# WS2812B.net
KiCad netlist of a schematic drawn in Altium Designer
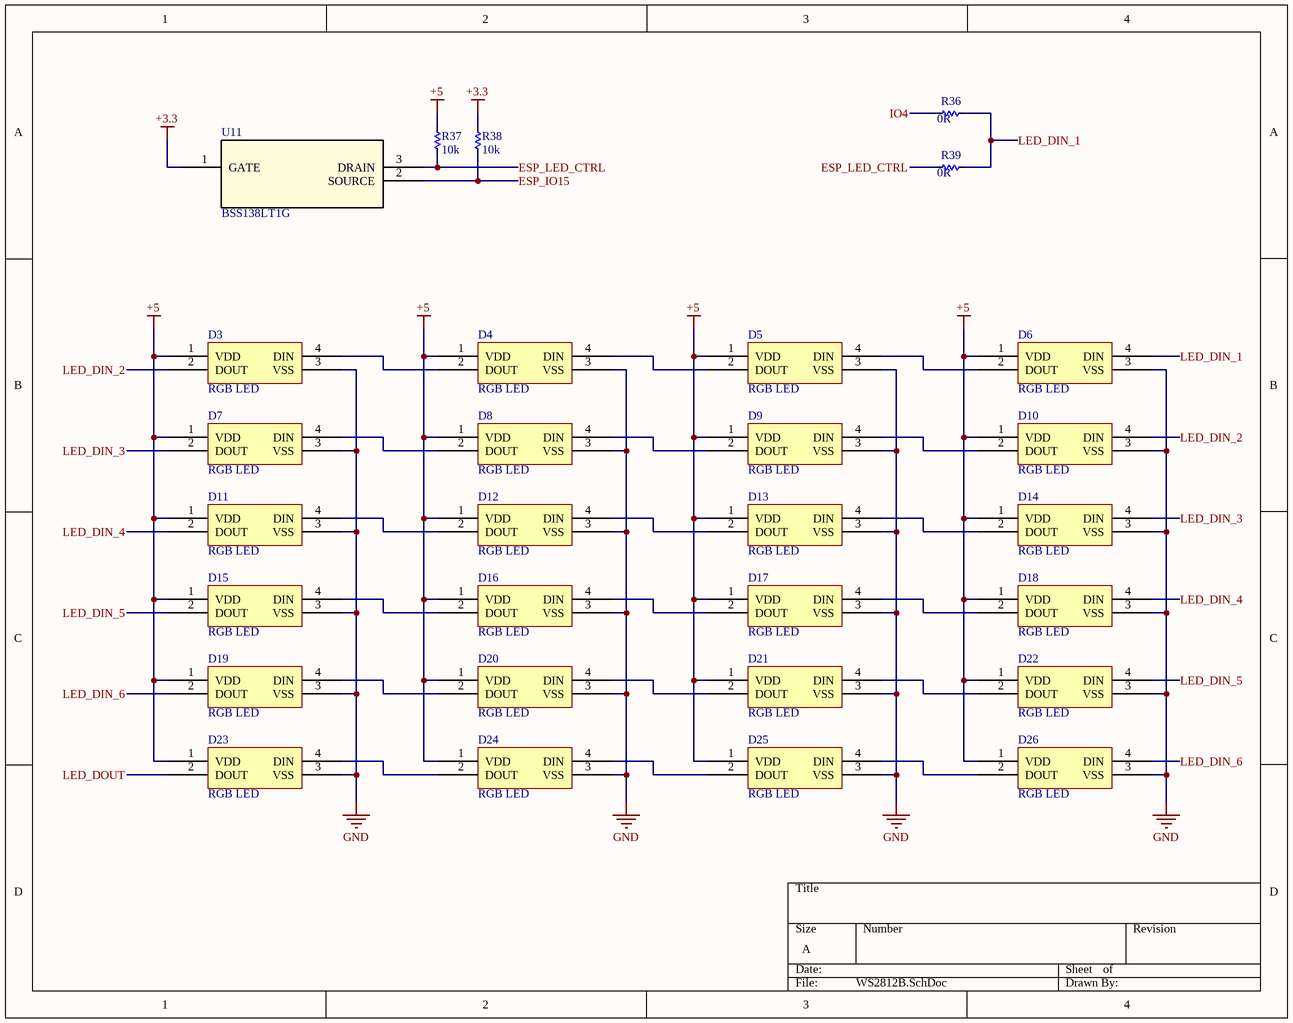
[diagram p0: WS2812B.SchDoc]

(export (version "E")
  (design (tool "Eeschema 10.0.6"))
  (components
    (comp (ref "D3")
      (value "RGB LED")
      (footprint "WS2812B")
      (description "RGB 620~630nm Red, 515~530nm Green, 465~475nm Blue SMD,5x5mm Light Emitting Diodes (LED) ROHS")
      (fields (field (name "MANUFACTURER") "Worldsemi"))
      (libsource (lib "WS2812B") (part "WS2812B"))
    )
    (comp (ref "D4")
      (value "RGB LED")
      (footprint "WS2812B")
      (description "RGB 620~630nm Red, 515~530nm Green, 465~475nm Blue SMD,5x5mm Light Emitting Diodes (LED) ROHS")
      (fields (field (name "MANUFACTURER") "Worldsemi"))
      (libsource (lib "WS2812B") (part "WS2812B"))
    )
    (comp (ref "D5")
      (value "RGB LED")
      (footprint "WS2812B")
      (description "RGB 620~630nm Red, 515~530nm Green, 465~475nm Blue SMD,5x5mm Light Emitting Diodes (LED) ROHS")
      (fields (field (name "MANUFACTURER") "Worldsemi"))
      (libsource (lib "WS2812B") (part "WS2812B"))
    )
    (comp (ref "D6")
      (value "RGB LED")
      (footprint "WS2812B")
      (description "RGB 620~630nm Red, 515~530nm Green, 465~475nm Blue SMD,5x5mm Light Emitting Diodes (LED) ROHS")
      (fields (field (name "MANUFACTURER") "Worldsemi"))
      (libsource (lib "WS2812B") (part "WS2812B"))
    )
    (comp (ref "D7")
      (value "RGB LED")
      (footprint "WS2812B")
      (description "RGB 620~630nm Red, 515~530nm Green, 465~475nm Blue SMD,5x5mm Light Emitting Diodes (LED) ROHS")
      (fields (field (name "MANUFACTURER") "Worldsemi"))
      (libsource (lib "WS2812B") (part "WS2812B"))
    )
    (comp (ref "D8")
      (value "RGB LED")
      (footprint "WS2812B")
      (description "RGB 620~630nm Red, 515~530nm Green, 465~475nm Blue SMD,5x5mm Light Emitting Diodes (LED) ROHS")
      (fields (field (name "MANUFACTURER") "Worldsemi"))
      (libsource (lib "WS2812B") (part "WS2812B"))
    )
    (comp (ref "D9")
      (value "RGB LED")
      (footprint "WS2812B")
      (description "RGB 620~630nm Red, 515~530nm Green, 465~475nm Blue SMD,5x5mm Light Emitting Diodes (LED) ROHS")
      (fields (field (name "MANUFACTURER") "Worldsemi"))
      (libsource (lib "WS2812B") (part "WS2812B"))
    )
    (comp (ref "D10")
      (value "RGB LED")
      (footprint "WS2812B")
      (description "RGB 620~630nm Red, 515~530nm Green, 465~475nm Blue SMD,5x5mm Light Emitting Diodes (LED) ROHS")
      (fields (field (name "MANUFACTURER") "Worldsemi"))
      (libsource (lib "WS2812B") (part "WS2812B"))
    )
    (comp (ref "D11")
      (value "RGB LED")
      (footprint "WS2812B")
      (description "RGB 620~630nm Red, 515~530nm Green, 465~475nm Blue SMD,5x5mm Light Emitting Diodes (LED) ROHS")
      (fields (field (name "MANUFACTURER") "Worldsemi"))
      (libsource (lib "WS2812B") (part "WS2812B"))
    )
    (comp (ref "D12")
      (value "RGB LED")
      (footprint "WS2812B")
      (description "RGB 620~630nm Red, 515~530nm Green, 465~475nm Blue SMD,5x5mm Light Emitting Diodes (LED) ROHS")
      (fields (field (name "MANUFACTURER") "Worldsemi"))
      (libsource (lib "WS2812B") (part "WS2812B"))
    )
    (comp (ref "D13")
      (value "RGB LED")
      (footprint "WS2812B")
      (description "RGB 620~630nm Red, 515~530nm Green, 465~475nm Blue SMD,5x5mm Light Emitting Diodes (LED) ROHS")
      (fields (field (name "MANUFACTURER") "Worldsemi"))
      (libsource (lib "WS2812B") (part "WS2812B"))
    )
    (comp (ref "D14")
      (value "RGB LED")
      (footprint "WS2812B")
      (description "RGB 620~630nm Red, 515~530nm Green, 465~475nm Blue SMD,5x5mm Light Emitting Diodes (LED) ROHS")
      (fields (field (name "MANUFACTURER") "Worldsemi"))
      (libsource (lib "WS2812B") (part "WS2812B"))
    )
    (comp (ref "D15")
      (value "RGB LED")
      (footprint "WS2812B")
      (description "RGB 620~630nm Red, 515~530nm Green, 465~475nm Blue SMD,5x5mm Light Emitting Diodes (LED) ROHS")
      (fields (field (name "MANUFACTURER") "Worldsemi"))
      (libsource (lib "WS2812B") (part "WS2812B"))
    )
    (comp (ref "D16")
      (value "RGB LED")
      (footprint "WS2812B")
      (description "RGB 620~630nm Red, 515~530nm Green, 465~475nm Blue SMD,5x5mm Light Emitting Diodes (LED) ROHS")
      (fields (field (name "MANUFACTURER") "Worldsemi"))
      (libsource (lib "WS2812B") (part "WS2812B"))
    )
    (comp (ref "D17")
      (value "RGB LED")
      (footprint "WS2812B")
      (description "RGB 620~630nm Red, 515~530nm Green, 465~475nm Blue SMD,5x5mm Light Emitting Diodes (LED) ROHS")
      (fields (field (name "MANUFACTURER") "Worldsemi"))
      (libsource (lib "WS2812B") (part "WS2812B"))
    )
    (comp (ref "D18")
      (value "RGB LED")
      (footprint "WS2812B")
      (description "RGB 620~630nm Red, 515~530nm Green, 465~475nm Blue SMD,5x5mm Light Emitting Diodes (LED) ROHS")
      (fields (field (name "MANUFACTURER") "Worldsemi"))
      (libsource (lib "WS2812B") (part "WS2812B"))
    )
    (comp (ref "D19")
      (value "RGB LED")
      (footprint "WS2812B")
      (description "RGB 620~630nm Red, 515~530nm Green, 465~475nm Blue SMD,5x5mm Light Emitting Diodes (LED) ROHS")
      (fields (field (name "MANUFACTURER") "Worldsemi"))
      (libsource (lib "WS2812B") (part "WS2812B"))
    )
    (comp (ref "D20")
      (value "RGB LED")
      (footprint "WS2812B")
      (description "RGB 620~630nm Red, 515~530nm Green, 465~475nm Blue SMD,5x5mm Light Emitting Diodes (LED) ROHS")
      (fields (field (name "MANUFACTURER") "Worldsemi"))
      (libsource (lib "WS2812B") (part "WS2812B"))
    )
    (comp (ref "D21")
      (value "RGB LED")
      (footprint "WS2812B")
      (description "RGB 620~630nm Red, 515~530nm Green, 465~475nm Blue SMD,5x5mm Light Emitting Diodes (LED) ROHS")
      (fields (field (name "MANUFACTURER") "Worldsemi"))
      (libsource (lib "WS2812B") (part "WS2812B"))
    )
    (comp (ref "D22")
      (value "RGB LED")
      (footprint "WS2812B")
      (description "RGB 620~630nm Red, 515~530nm Green, 465~475nm Blue SMD,5x5mm Light Emitting Diodes (LED) ROHS")
      (fields (field (name "MANUFACTURER") "Worldsemi"))
      (libsource (lib "WS2812B") (part "WS2812B"))
    )
    (comp (ref "D23")
      (value "RGB LED")
      (footprint "WS2812B")
      (description "RGB 620~630nm Red, 515~530nm Green, 465~475nm Blue SMD,5x5mm Light Emitting Diodes (LED) ROHS")
      (fields (field (name "MANUFACTURER") "Worldsemi"))
      (libsource (lib "WS2812B") (part "WS2812B"))
    )
    (comp (ref "D24")
      (value "RGB LED")
      (footprint "WS2812B")
      (description "RGB 620~630nm Red, 515~530nm Green, 465~475nm Blue SMD,5x5mm Light Emitting Diodes (LED) ROHS")
      (fields (field (name "MANUFACTURER") "Worldsemi"))
      (libsource (lib "WS2812B") (part "WS2812B"))
    )
    (comp (ref "D25")
      (value "RGB LED")
      (footprint "WS2812B")
      (description "RGB 620~630nm Red, 515~530nm Green, 465~475nm Blue SMD,5x5mm Light Emitting Diodes (LED) ROHS")
      (fields (field (name "MANUFACTURER") "Worldsemi"))
      (libsource (lib "WS2812B") (part "WS2812B"))
    )
    (comp (ref "D26")
      (value "RGB LED")
      (footprint "WS2812B")
      (description "RGB 620~630nm Red, 515~530nm Green, 465~475nm Blue SMD,5x5mm Light Emitting Diodes (LED) ROHS")
      (fields (field (name "MANUFACTURER") "Worldsemi"))
      (libsource (lib "WS2812B") (part "WS2812B"))
    )
    (comp (ref "R36")
      (value "0R")
      (footprint "RES-SMD-0603")
      (description "Resistor")
      (fields
        (field (name "MANUFACTURER") "Generic Components")
        (field (name "Comment") "Res")
        (field (name "PUBLISHER") "Altium Hobart Technology Centre")
      )
      (libsource (lib "LIBRARY") (part "Res-SMD"))
    )
    (comp (ref "R37")
      (value "10k")
      (footprint "RES-SMD-0603")
      (description "Resistor")
      (fields
        (field (name "MANUFACTURER") "Generic Components")
        (field (name "Comment") "Res")
        (field (name "PUBLISHER") "Altium Hobart Technology Centre")
      )
      (libsource (lib "LIBRARY") (part "Res-SMD"))
    )
    (comp (ref "R38")
      (value "10k")
      (footprint "RES-SMD-0603")
      (description "Resistor")
      (fields
        (field (name "MANUFACTURER") "Generic Components")
        (field (name "Comment") "Res")
        (field (name "PUBLISHER") "Altium Hobart Technology Centre")
      )
      (libsource (lib "LIBRARY") (part "Res-SMD"))
    )
    (comp (ref "R39")
      (value "0R")
      (footprint "RES-SMD-0603")
      (description "Resistor")
      (fields
        (field (name "MANUFACTURER") "Generic Components")
        (field (name "Comment") "Res")
        (field (name "PUBLISHER") "Altium Hobart Technology Centre")
      )
      (libsource (lib "LIBRARY") (part "Res-SMD"))
    )
    (comp (ref "U11")
      (value "BSS138LT1G")
      (footprint "SOT23-3_ONS")
      (description "No Description Available")
      (fields (field (name "COPYRIGHT") "Copyright (C) 2018 Accelerated Designs. All rights reserved"))
      (libsource (lib "BSS138LT1G") (part "BSS138LT1G"))
    )
  )
  (nets
    (net (code "1") (name "+3.3") (class "Default")
      (node (ref "R38") (pin "1") (pinfunction "1_1") (pintype "passive"))
      (node (ref "U11") (pin "1") (pinfunction "GATE_1") (pintype "passive"))
    )
    (net (code "2") (name "+5") (class "Default")
      (node (ref "D10") (pin "1") (pinfunction "VDD_1") (pintype "passive"))
      (node (ref "D11") (pin "1") (pinfunction "VDD_1") (pintype "passive"))
      (node (ref "D12") (pin "1") (pinfunction "VDD_1") (pintype "passive"))
      (node (ref "D13") (pin "1") (pinfunction "VDD_1") (pintype "passive"))
      (node (ref "D14") (pin "1") (pinfunction "VDD_1") (pintype "passive"))
      (node (ref "D15") (pin "1") (pinfunction "VDD_1") (pintype "passive"))
      (node (ref "D16") (pin "1") (pinfunction "VDD_1") (pintype "passive"))
      (node (ref "D17") (pin "1") (pinfunction "VDD_1") (pintype "passive"))
      (node (ref "D18") (pin "1") (pinfunction "VDD_1") (pintype "passive"))
      (node (ref "D19") (pin "1") (pinfunction "VDD_1") (pintype "passive"))
      (node (ref "D20") (pin "1") (pinfunction "VDD_1") (pintype "passive"))
      (node (ref "D21") (pin "1") (pinfunction "VDD_1") (pintype "passive"))
      (node (ref "D22") (pin "1") (pinfunction "VDD_1") (pintype "passive"))
      (node (ref "D23") (pin "1") (pinfunction "VDD_1") (pintype "passive"))
      (node (ref "D24") (pin "1") (pinfunction "VDD_1") (pintype "passive"))
      (node (ref "D25") (pin "1") (pinfunction "VDD_1") (pintype "passive"))
      (node (ref "D26") (pin "1") (pinfunction "VDD_1") (pintype "passive"))
      (node (ref "D3") (pin "1") (pinfunction "VDD_1") (pintype "passive"))
      (node (ref "D4") (pin "1") (pinfunction "VDD_1") (pintype "passive"))
      (node (ref "D5") (pin "1") (pinfunction "VDD_1") (pintype "passive"))
      (node (ref "D6") (pin "1") (pinfunction "VDD_1") (pintype "passive"))
      (node (ref "D7") (pin "1") (pinfunction "VDD_1") (pintype "passive"))
      (node (ref "D8") (pin "1") (pinfunction "VDD_1") (pintype "passive"))
      (node (ref "D9") (pin "1") (pinfunction "VDD_1") (pintype "passive"))
      (node (ref "R37") (pin "1") (pinfunction "1_1") (pintype "passive"))
    )
    (net (code "3") (name "/ESP_IO15") (class "Default")
      (node (ref "R38") (pin "2") (pinfunction "2_2") (pintype "passive"))
      (node (ref "U11") (pin "2") (pinfunction "SOURCE_2") (pintype "passive"))
    )
    (net (code "4") (name "/ESP_LED_CTRL") (class "Default")
      (node (ref "R37") (pin "2") (pinfunction "2_2") (pintype "passive"))
      (node (ref "R39") (pin "2") (pinfunction "2_2") (pintype "passive"))
      (node (ref "U11") (pin "3") (pinfunction "DRAIN_3") (pintype "passive"))
    )
    (net (code "5") (name "/IO4") (class "Default")
      (node (ref "R36") (pin "2") (pinfunction "2_2") (pintype "passive"))
    )
    (net (code "6") (name "/LED_DIN_1") (class "Default")
      (node (ref "D6") (pin "4") (pinfunction "DIN_4") (pintype "passive"))
      (node (ref "R36") (pin "1") (pinfunction "1_1") (pintype "passive"))
      (node (ref "R39") (pin "1") (pinfunction "1_1") (pintype "passive"))
    )
    (net (code "7") (name "/LED_DIN_2") (class "Default")
      (node (ref "D10") (pin "4") (pinfunction "DIN_4") (pintype "passive"))
      (node (ref "D3") (pin "2") (pinfunction "DOUT_2") (pintype "passive"))
    )
    (net (code "8") (name "/LED_DIN_3") (class "Default")
      (node (ref "D14") (pin "4") (pinfunction "DIN_4") (pintype "passive"))
      (node (ref "D7") (pin "2") (pinfunction "DOUT_2") (pintype "passive"))
    )
    (net (code "9") (name "/LED_DIN_4") (class "Default")
      (node (ref "D11") (pin "2") (pinfunction "DOUT_2") (pintype "passive"))
      (node (ref "D18") (pin "4") (pinfunction "DIN_4") (pintype "passive"))
    )
    (net (code "10") (name "/LED_DIN_5") (class "Default")
      (node (ref "D15") (pin "2") (pinfunction "DOUT_2") (pintype "passive"))
      (node (ref "D22") (pin "4") (pinfunction "DIN_4") (pintype "passive"))
    )
    (net (code "11") (name "/LED_DIN_6") (class "Default")
      (node (ref "D19") (pin "2") (pinfunction "DOUT_2") (pintype "passive"))
      (node (ref "D26") (pin "4") (pinfunction "DIN_4") (pintype "passive"))
    )
    (net (code "12") (name "/LED_DOUT") (class "Default")
      (node (ref "D23") (pin "2") (pinfunction "DOUT_2") (pintype "passive"))
    )
    (net (code "13") (name "GND") (class "Default")
      (node (ref "D10") (pin "3") (pinfunction "VSS_3") (pintype "passive"))
      (node (ref "D11") (pin "3") (pinfunction "VSS_3") (pintype "passive"))
      (node (ref "D12") (pin "3") (pinfunction "VSS_3") (pintype "passive"))
      (node (ref "D13") (pin "3") (pinfunction "VSS_3") (pintype "passive"))
      (node (ref "D14") (pin "3") (pinfunction "VSS_3") (pintype "passive"))
      (node (ref "D15") (pin "3") (pinfunction "VSS_3") (pintype "passive"))
      (node (ref "D16") (pin "3") (pinfunction "VSS_3") (pintype "passive"))
      (node (ref "D17") (pin "3") (pinfunction "VSS_3") (pintype "passive"))
      (node (ref "D18") (pin "3") (pinfunction "VSS_3") (pintype "passive"))
      (node (ref "D19") (pin "3") (pinfunction "VSS_3") (pintype "passive"))
      (node (ref "D20") (pin "3") (pinfunction "VSS_3") (pintype "passive"))
      (node (ref "D21") (pin "3") (pinfunction "VSS_3") (pintype "passive"))
      (node (ref "D22") (pin "3") (pinfunction "VSS_3") (pintype "passive"))
      (node (ref "D23") (pin "3") (pinfunction "VSS_3") (pintype "passive"))
      (node (ref "D24") (pin "3") (pinfunction "VSS_3") (pintype "passive"))
      (node (ref "D25") (pin "3") (pinfunction "VSS_3") (pintype "passive"))
      (node (ref "D26") (pin "3") (pinfunction "VSS_3") (pintype "passive"))
      (node (ref "D3") (pin "3") (pinfunction "VSS_3") (pintype "passive"))
      (node (ref "D4") (pin "3") (pinfunction "VSS_3") (pintype "passive"))
      (node (ref "D5") (pin "3") (pinfunction "VSS_3") (pintype "passive"))
      (node (ref "D6") (pin "3") (pinfunction "VSS_3") (pintype "passive"))
      (node (ref "D7") (pin "3") (pinfunction "VSS_3") (pintype "passive"))
      (node (ref "D8") (pin "3") (pinfunction "VSS_3") (pintype "passive"))
      (node (ref "D9") (pin "3") (pinfunction "VSS_3") (pintype "passive"))
    )
    (net (code "14") (name "Net-(D3-DIN)") (class "Default")
      (node (ref "D3") (pin "4") (pinfunction "DIN_4") (pintype "passive"))
      (node (ref "D4") (pin "2") (pinfunction "DOUT_2") (pintype "passive"))
    )
    (net (code "15") (name "Net-(D4-DIN)") (class "Default")
      (node (ref "D4") (pin "4") (pinfunction "DIN_4") (pintype "passive"))
      (node (ref "D5") (pin "2") (pinfunction "DOUT_2") (pintype "passive"))
    )
    (net (code "16") (name "Net-(D5-DIN)") (class "Default")
      (node (ref "D5") (pin "4") (pinfunction "DIN_4") (pintype "passive"))
      (node (ref "D6") (pin "2") (pinfunction "DOUT_2") (pintype "passive"))
    )
    (net (code "17") (name "Net-(D7-DIN)") (class "Default")
      (node (ref "D7") (pin "4") (pinfunction "DIN_4") (pintype "passive"))
      (node (ref "D8") (pin "2") (pinfunction "DOUT_2") (pintype "passive"))
    )
    (net (code "18") (name "Net-(D8-DIN)") (class "Default")
      (node (ref "D8") (pin "4") (pinfunction "DIN_4") (pintype "passive"))
      (node (ref "D9") (pin "2") (pinfunction "DOUT_2") (pintype "passive"))
    )
    (net (code "19") (name "Net-(D10-DOUT)") (class "Default")
      (node (ref "D10") (pin "2") (pinfunction "DOUT_2") (pintype "passive"))
      (node (ref "D9") (pin "4") (pinfunction "DIN_4") (pintype "passive"))
    )
    (net (code "20") (name "Net-(D11-DIN)") (class "Default")
      (node (ref "D11") (pin "4") (pinfunction "DIN_4") (pintype "passive"))
      (node (ref "D12") (pin "2") (pinfunction "DOUT_2") (pintype "passive"))
    )
    (net (code "21") (name "Net-(D12-DIN)") (class "Default")
      (node (ref "D12") (pin "4") (pinfunction "DIN_4") (pintype "passive"))
      (node (ref "D13") (pin "2") (pinfunction "DOUT_2") (pintype "passive"))
    )
    (net (code "22") (name "Net-(D13-DIN)") (class "Default")
      (node (ref "D13") (pin "4") (pinfunction "DIN_4") (pintype "passive"))
      (node (ref "D14") (pin "2") (pinfunction "DOUT_2") (pintype "passive"))
    )
    (net (code "23") (name "Net-(D15-DIN)") (class "Default")
      (node (ref "D15") (pin "4") (pinfunction "DIN_4") (pintype "passive"))
      (node (ref "D16") (pin "2") (pinfunction "DOUT_2") (pintype "passive"))
    )
    (net (code "24") (name "Net-(D16-DIN)") (class "Default")
      (node (ref "D16") (pin "4") (pinfunction "DIN_4") (pintype "passive"))
      (node (ref "D17") (pin "2") (pinfunction "DOUT_2") (pintype "passive"))
    )
    (net (code "25") (name "Net-(D17-DIN)") (class "Default")
      (node (ref "D17") (pin "4") (pinfunction "DIN_4") (pintype "passive"))
      (node (ref "D18") (pin "2") (pinfunction "DOUT_2") (pintype "passive"))
    )
    (net (code "26") (name "Net-(D19-DIN)") (class "Default")
      (node (ref "D19") (pin "4") (pinfunction "DIN_4") (pintype "passive"))
      (node (ref "D20") (pin "2") (pinfunction "DOUT_2") (pintype "passive"))
    )
    (net (code "27") (name "Net-(D20-DIN)") (class "Default")
      (node (ref "D20") (pin "4") (pinfunction "DIN_4") (pintype "passive"))
      (node (ref "D21") (pin "2") (pinfunction "DOUT_2") (pintype "passive"))
    )
    (net (code "28") (name "Net-(D21-DIN)") (class "Default")
      (node (ref "D21") (pin "4") (pinfunction "DIN_4") (pintype "passive"))
      (node (ref "D22") (pin "2") (pinfunction "DOUT_2") (pintype "passive"))
    )
    (net (code "29") (name "Net-(D23-DIN)") (class "Default")
      (node (ref "D23") (pin "4") (pinfunction "DIN_4") (pintype "passive"))
      (node (ref "D24") (pin "2") (pinfunction "DOUT_2") (pintype "passive"))
    )
    (net (code "30") (name "Net-(D24-DIN)") (class "Default")
      (node (ref "D24") (pin "4") (pinfunction "DIN_4") (pintype "passive"))
      (node (ref "D25") (pin "2") (pinfunction "DOUT_2") (pintype "passive"))
    )
    (net (code "31") (name "Net-(D25-DIN)") (class "Default")
      (node (ref "D25") (pin "4") (pinfunction "DIN_4") (pintype "passive"))
      (node (ref "D26") (pin "2") (pinfunction "DOUT_2") (pintype "passive"))
    )
  )
)
